# Sheet1.net
KiCad netlist of a schematic drawn in Altium Designer
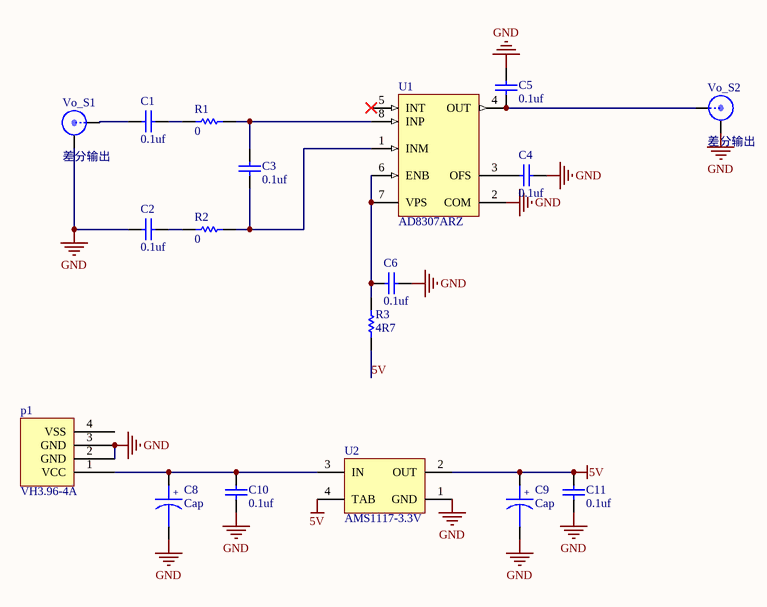
[diagram p0: Sheet1.SchDoc]

(export (version "E")
  (design (tool "Eeschema 10.0.6"))
  (components
    (comp (ref "C1") (value "0.1uf") (footprint "0603C") (libsource (lib "Schlib1") (part "Cap")))
    (comp (ref "C2") (value "0.1uf") (footprint "0603C") (libsource (lib "Schlib1") (part "Cap")))
    (comp (ref "C3") (value "0.1uf") (footprint "0603C") (libsource (lib "Schlib1") (part "Cap")))
    (comp (ref "C4") (value "0.1uf") (footprint "0805") (libsource (lib "Schlib1") (part "Cap")))
    (comp (ref "C5") (value "0.1uf") (footprint "0805") (libsource (lib "Schlib1") (part "Cap")))
    (comp (ref "C6") (value "0.1uf") (footprint "0805") (libsource (lib "Schlib1") (part "Cap")))
    (comp (ref "C8")
      (value "Cap")
      (footprint "3216C-TYPE_A")
      (libsource (lib "Schlib1") (part "Tantalium Cap"))
    )
    (comp (ref "C9")
      (value "Cap")
      (footprint "3216C-TYPE_A")
      (libsource (lib "Schlib1") (part "Tantalium Cap"))
    )
    (comp (ref "C10") (value "0.1uf") (footprint "0805") (libsource (lib "Schlib1") (part "Cap")))
    (comp (ref "C11") (value "0.1uf") (footprint "0805") (libsource (lib "Schlib1") (part "Cap")))
    (comp (ref "p1")
      (value "VH3.96-4A")
      (footprint "VH3.96-4P")
      (libsource (lib "Schlib1") (part "VH3.96-4A"))
    )
    (comp (ref "R1") (value "0") (footprint "0603R") (libsource (lib "Schlib1") (part "Res")))
    (comp (ref "R2") (value "0") (footprint "0603R") (libsource (lib "Schlib1") (part "Res")))
    (comp (ref "R3") (value "4R7") (footprint "0805") (libsource (lib "Schlib1") (part "Res")))
    (comp (ref "U1")
      (value "AD8307ARZ")
      (footprint "ADI-R-8_N")
      (description "Low Cost, DC to 500 MHz, 92 dB Logarithmic Amplifier, 400ns Response Time, R-8, Pb-Free, 98 Tube")
      (libsource (lib "Schlib1") (part "AD8307ARZ"))
    )
    (comp (ref "U2")
      (value "AMS1117-3.3V")
      (footprint "SOT-223")
      (libsource (lib "Schlib1") (part "AMS1117-3.3V"))
    )
    (comp (ref "Vo_S1") (value "差分输出") (footprint "SMA-LYING") (libsource (lib "Schlib1") (part "SMA")))
    (comp (ref "Vo_S2") (value "差分输出") (footprint "SMA-LYING") (libsource (lib "Schlib1") (part "SMA")))
  )
  (nets
    (net (code "1") (name "5V") (class "Default")
      (node (ref "C11") (pin "2") (pinfunction "2_2") (pintype "passive"))
      (node (ref "C9") (pin "1") (pinfunction "1_1") (pintype "passive"))
      (node (ref "R3") (pin "1") (pinfunction "1_1") (pintype "passive"))
      (node (ref "U2") (pin "2") (pinfunction "OUT_2") (pintype "power_in"))
      (node (ref "U2") (pin "4") (pinfunction "TAB_4") (pintype "power_in"))
    )
    (net (code "2") (name "GND") (class "Default")
      (node (ref "C10") (pin "1") (pinfunction "1_1") (pintype "passive"))
      (node (ref "C11") (pin "1") (pinfunction "1_1") (pintype "passive"))
      (node (ref "C2") (pin "1") (pinfunction "1_1") (pintype "passive"))
      (node (ref "C4") (pin "2") (pinfunction "2_2") (pintype "passive"))
      (node (ref "C5") (pin "2") (pinfunction "2_2") (pintype "passive"))
      (node (ref "C6") (pin "2") (pinfunction "2_2") (pintype "passive"))
      (node (ref "C8") (pin "2") (pinfunction "2_2") (pintype "passive"))
      (node (ref "C9") (pin "2") (pinfunction "2_2") (pintype "passive"))
      (node (ref "U1") (pin "2") (pinfunction "COM_2") (pintype "power_in"))
      (node (ref "U2") (pin "1") (pinfunction "GND_1") (pintype "power_in"))
      (node (ref "Vo_S1") (pin "1") (pinfunction "1_1") (pintype "passive"))
      (node (ref "Vo_S2") (pin "1") (pinfunction "1_1") (pintype "passive"))
      (node (ref "p1") (pin "2") (pinfunction "GND_2") (pintype "passive"))
      (node (ref "p1") (pin "3") (pinfunction "GND_3") (pintype "passive"))
    )
    (net (code "3") (name "Net-(C1-Pad1)") (class "Default")
      (node (ref "C1") (pin "1") (pinfunction "1_1") (pintype "passive"))
      (node (ref "Vo_S1") (pin "0") (pinfunction "0_0") (pintype "passive"))
    )
    (net (code "4") (name "Net-(C1-Pad2)") (class "Default")
      (node (ref "C1") (pin "2") (pinfunction "2_2") (pintype "passive"))
      (node (ref "R1") (pin "1") (pinfunction "1_1") (pintype "passive"))
    )
    (net (code "5") (name "Net-(C2-Pad2)") (class "Default")
      (node (ref "C2") (pin "2") (pinfunction "2_2") (pintype "passive"))
      (node (ref "R2") (pin "1") (pinfunction "1_1") (pintype "passive"))
    )
    (net (code "6") (name "Net-(U1-ENB)") (class "Default")
      (node (ref "C6") (pin "1") (pinfunction "1_1") (pintype "passive"))
      (node (ref "R3") (pin "2") (pinfunction "2_2") (pintype "passive"))
      (node (ref "U1") (pin "6") (pinfunction "ENB_6") (pintype "input"))
      (node (ref "U1") (pin "7") (pinfunction "VPS_7") (pintype "power_in"))
    )
    (net (code "7") (name "Net-(U1-INM)") (class "Default")
      (node (ref "C3") (pin "1") (pinfunction "1_1") (pintype "passive"))
      (node (ref "R2") (pin "2") (pinfunction "2_2") (pintype "passive"))
      (node (ref "U1") (pin "1") (pinfunction "INM_1") (pintype "input"))
    )
    (net (code "8") (name "Net-(U1-INP)") (class "Default")
      (node (ref "C3") (pin "2") (pinfunction "2_2") (pintype "passive"))
      (node (ref "R1") (pin "2") (pinfunction "2_2") (pintype "passive"))
      (node (ref "U1") (pin "8") (pinfunction "INP_8") (pintype "input"))
    )
    (net (code "9") (name "Net-(U1-OFS)") (class "Default")
      (node (ref "C4") (pin "1") (pinfunction "1_1") (pintype "passive"))
      (node (ref "U1") (pin "3") (pinfunction "OFS_3") (pintype "passive"))
    )
    (net (code "10") (name "Net-(U1-OUT)") (class "Default")
      (node (ref "C5") (pin "1") (pinfunction "1_1") (pintype "passive"))
      (node (ref "U1") (pin "4") (pinfunction "OUT_4") (pintype "output"))
      (node (ref "Vo_S2") (pin "0") (pinfunction "0_0") (pintype "passive"))
    )
    (net (code "11") (name "Net-(U2-IN)") (class "Default")
      (node (ref "C10") (pin "2") (pinfunction "2_2") (pintype "passive"))
      (node (ref "C8") (pin "1") (pinfunction "1_1") (pintype "passive"))
      (node (ref "U2") (pin "3") (pinfunction "IN_3") (pintype "power_in"))
      (node (ref "p1") (pin "1") (pinfunction "VCC_1") (pintype "passive"))
    )
    (net (code "12") (name "unconnected-(U1-INT-Pad5)") (class "Default")
      (node (ref "U1") (pin "5") (pinfunction "INT_5") (pintype "input+no_connect"))
    )
    (net (code "13") (name "unconnected-(p1-VSS-Pad4)") (class "Default")
      (node (ref "p1") (pin "4") (pinfunction "VSS_4") (pintype "passive"))
    )
  )
)
